# ProPrj_VEX_Competition_Switch_Duo_2025-0.net
KiCad netlist of a schematic drawn in EasyEDA Pro
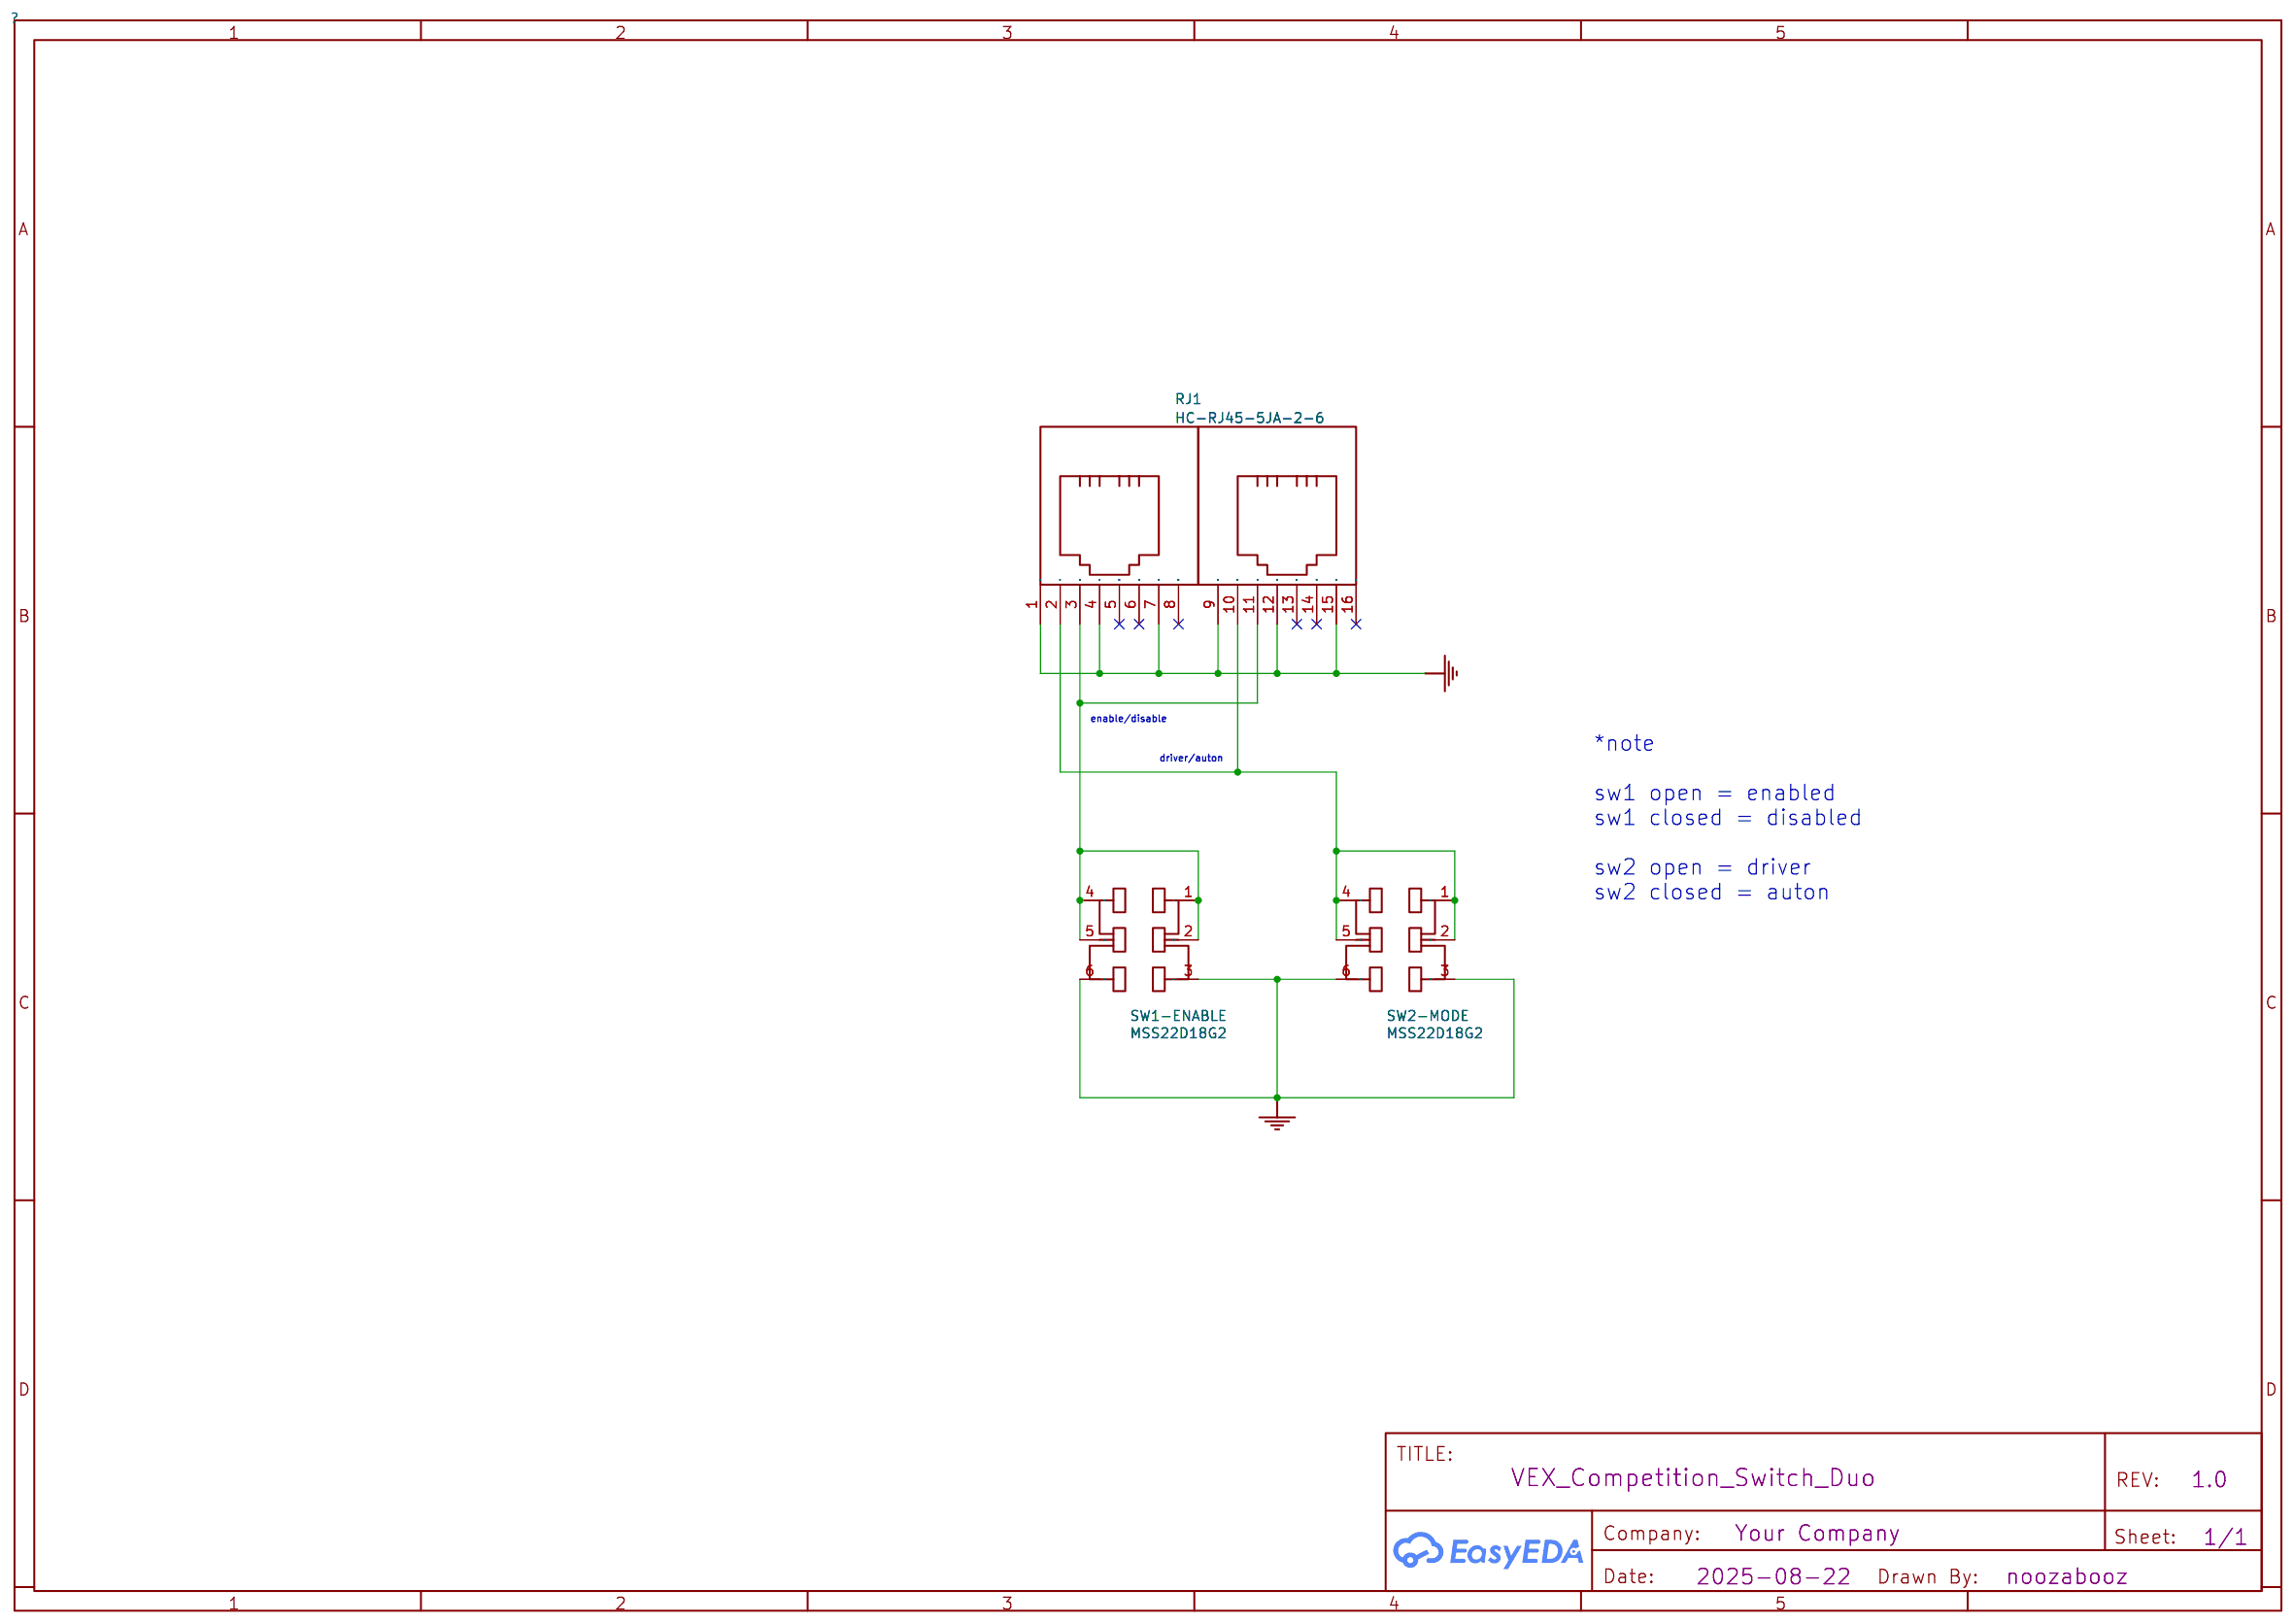
[diagram p0: schematic sheet]

(export (version "E")
  (design (tool "Eeschema 10.0.6"))
  (components
    (comp (ref "RJ1")
      (value "HC-RJ45-5JA-2-6")
      (footprint "easyedapro:RJ45-TH_HC-RJ45-5JA-2-6-S")
      (fields (field (name "Manufacturer") "HCTL(华灿天禄)") (field (name "Contributor") "lcsc"))
      (libsource (lib "easyedapro") (part "HC-RJ45-5JA-2-6"))
    )
    (comp (ref "SW1-ENABLE")
      (value "MSS22D18G2")
      (footprint "easyedapro:SW-TH_MSS22D18GX")
      (fields (field (name "Manufacturer") "SHOU HAN(首韩)") (field (name "Contributor") "LCSC"))
      (libsource (lib "easyedapro") (part "MSS22D18G2"))
    )
    (comp (ref "SW2-MODE")
      (value "MSS22D18G2")
      (footprint "easyedapro:SW-TH_MSS22D18GX")
      (fields (field (name "Manufacturer") "SHOU HAN(首韩)") (field (name "Contributor") "LCSC"))
      (libsource (lib "easyedapro") (part "MSS22D18G2"))
    )
  )
  (nets
    (net (code "1") (name "GND") (class "Default")
      (node (ref "RJ1") (pin "1") (pinfunction "1_1") (pintype "unspecified"))
      (node (ref "RJ1") (pin "12") (pinfunction "12_12") (pintype "unspecified"))
      (node (ref "RJ1") (pin "15") (pinfunction "15_15") (pintype "unspecified"))
      (node (ref "RJ1") (pin "4") (pinfunction "4_4") (pintype "unspecified"))
      (node (ref "RJ1") (pin "7") (pinfunction "7_7") (pintype "unspecified"))
      (node (ref "RJ1") (pin "9") (pinfunction "9_9") (pintype "unspecified"))
      (node (ref "SW1-ENABLE") (pin "3") (pinfunction "3_3") (pintype "unspecified"))
      (node (ref "SW1-ENABLE") (pin "6") (pinfunction "6_6") (pintype "unspecified"))
      (node (ref "SW2-MODE") (pin "3") (pinfunction "3_3") (pintype "unspecified"))
      (node (ref "SW2-MODE") (pin "6") (pinfunction "6_6") (pintype "unspecified"))
    )
    (net (code "2") (name "Net-(RJ1-Pad10)") (class "Default")
      (node (ref "RJ1") (pin "10") (pinfunction "10_10") (pintype "unspecified"))
      (node (ref "RJ1") (pin "2") (pinfunction "2_2") (pintype "unspecified"))
      (node (ref "SW2-MODE") (pin "1") (pinfunction "1_1") (pintype "unspecified"))
      (node (ref "SW2-MODE") (pin "2") (pinfunction "2_2") (pintype "unspecified"))
      (node (ref "SW2-MODE") (pin "4") (pinfunction "4_4") (pintype "unspecified"))
      (node (ref "SW2-MODE") (pin "5") (pinfunction "5_5") (pintype "unspecified"))
    )
    (net (code "3") (name "Net-(RJ1-Pad11)") (class "Default")
      (node (ref "RJ1") (pin "11") (pinfunction "11_11") (pintype "unspecified"))
      (node (ref "RJ1") (pin "3") (pinfunction "3_3") (pintype "unspecified"))
      (node (ref "SW1-ENABLE") (pin "1") (pinfunction "1_1") (pintype "unspecified"))
      (node (ref "SW1-ENABLE") (pin "2") (pinfunction "2_2") (pintype "unspecified"))
      (node (ref "SW1-ENABLE") (pin "4") (pinfunction "4_4") (pintype "unspecified"))
      (node (ref "SW1-ENABLE") (pin "5") (pinfunction "5_5") (pintype "unspecified"))
    )
    (net (code "4") (name "unconnected-(RJ1-Pad5)") (class "Default")
      (node (ref "RJ1") (pin "5") (pinfunction "5_5") (pintype "unspecified+no_connect"))
    )
    (net (code "5") (name "unconnected-(RJ1-Pad6)") (class "Default")
      (node (ref "RJ1") (pin "6") (pinfunction "6_6") (pintype "unspecified+no_connect"))
    )
    (net (code "6") (name "unconnected-(RJ1-Pad8)") (class "Default")
      (node (ref "RJ1") (pin "8") (pinfunction "8_8") (pintype "unspecified+no_connect"))
    )
    (net (code "7") (name "unconnected-(RJ1-Pad13)") (class "Default")
      (node (ref "RJ1") (pin "13") (pinfunction "13_13") (pintype "unspecified+no_connect"))
    )
    (net (code "8") (name "unconnected-(RJ1-Pad14)") (class "Default")
      (node (ref "RJ1") (pin "14") (pinfunction "14_14") (pintype "unspecified+no_connect"))
    )
    (net (code "9") (name "unconnected-(RJ1-Pad16)") (class "Default")
      (node (ref "RJ1") (pin "16") (pinfunction "16_16") (pintype "unspecified+no_connect"))
    )
  )
)
